# Vumetro.net
KiCad netlist of a schematic drawn in EAGLE
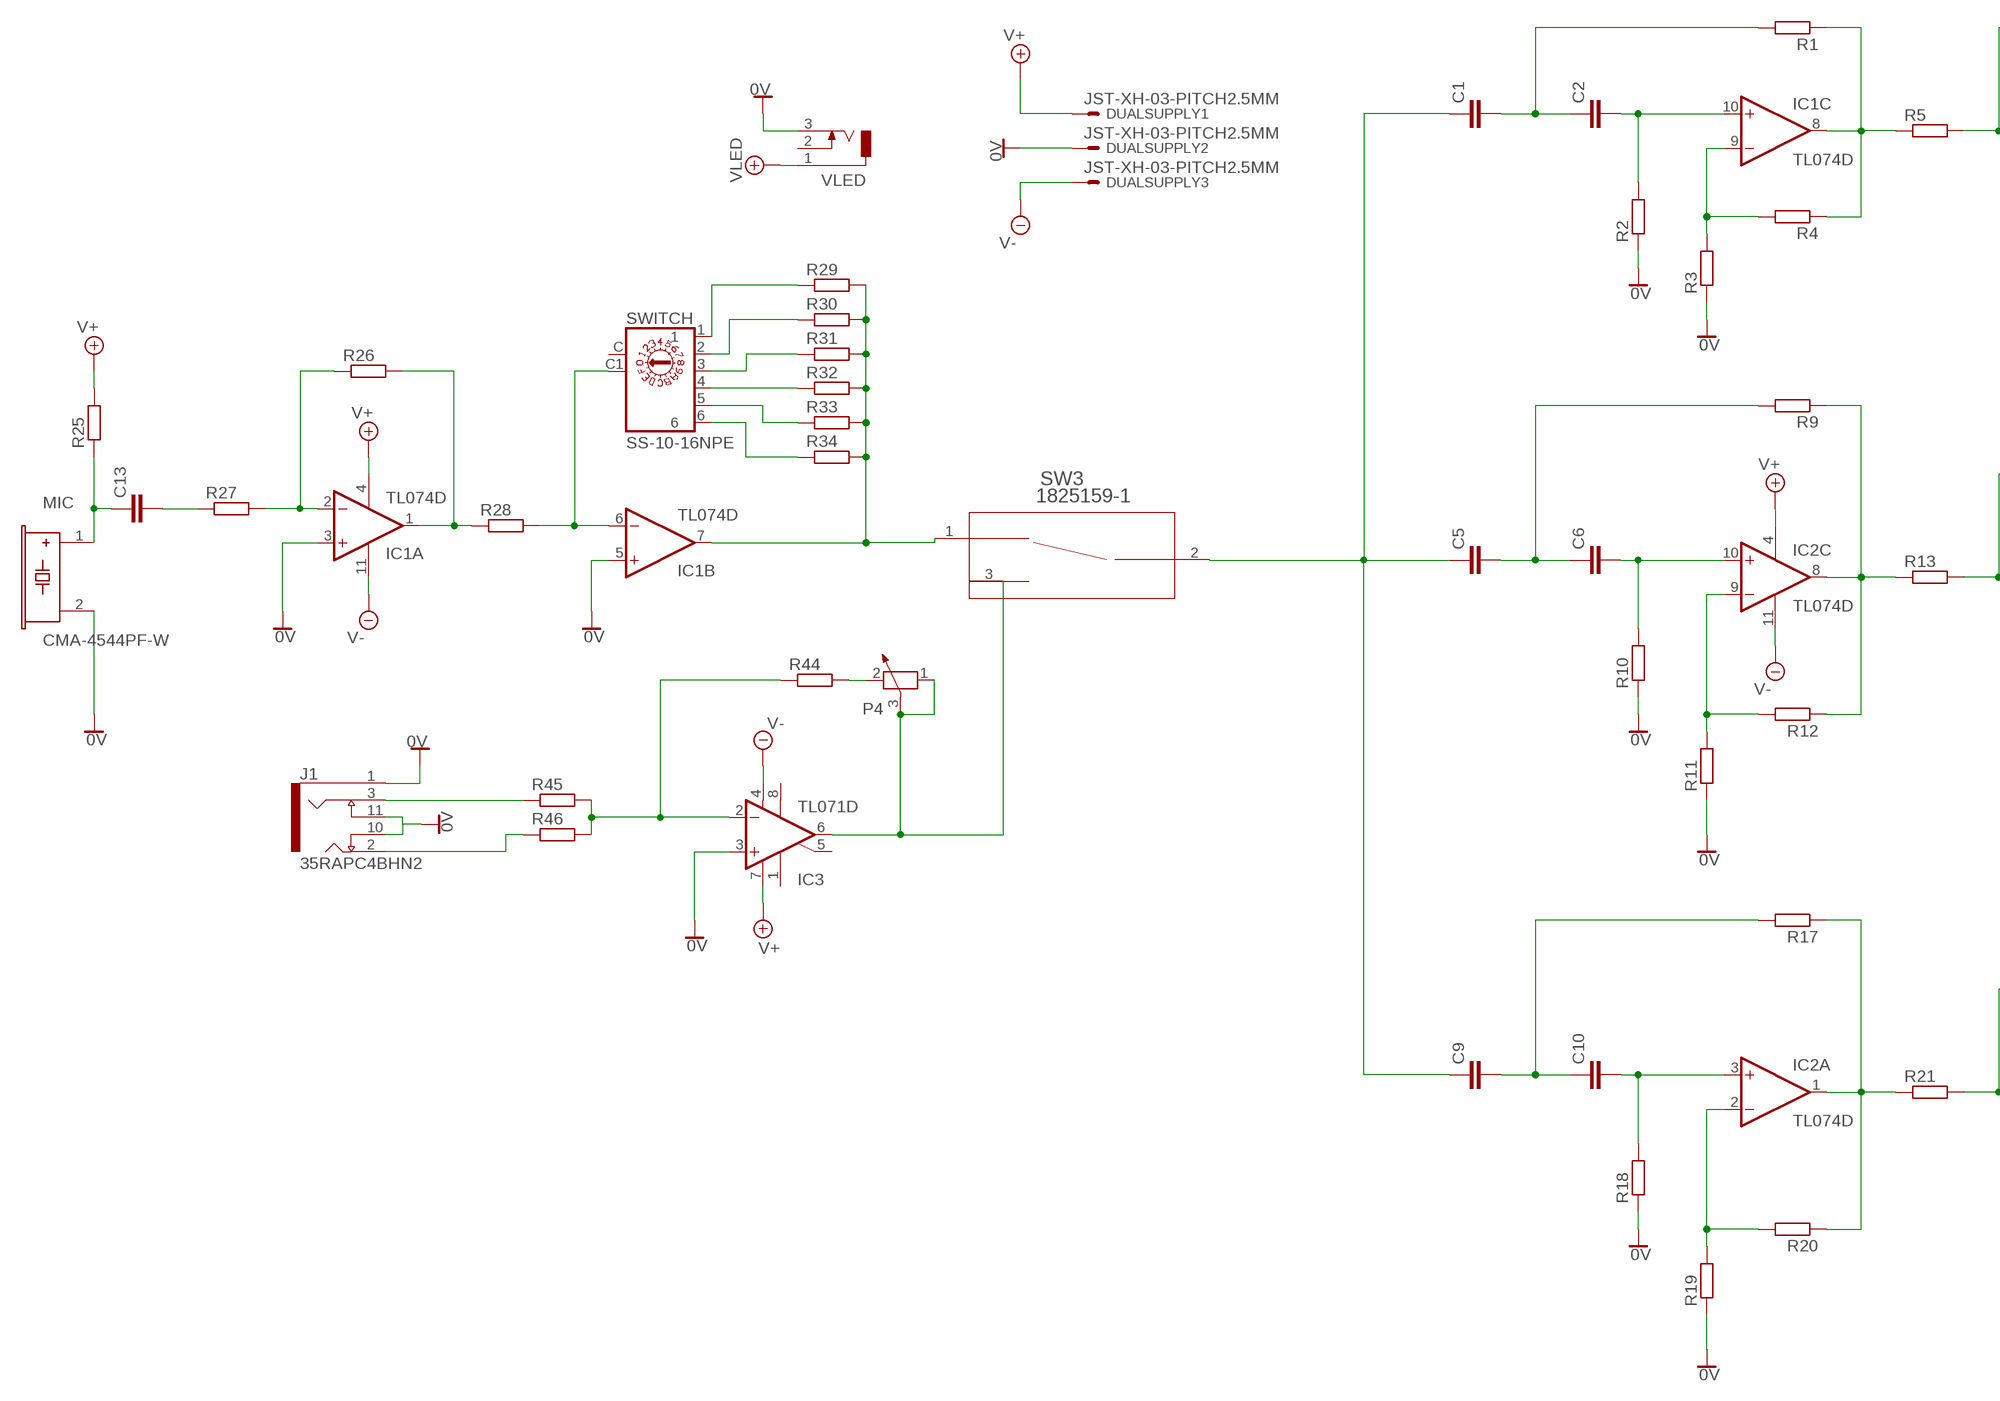
[diagram p0: schematic, sheet 1, part 1 of 2]
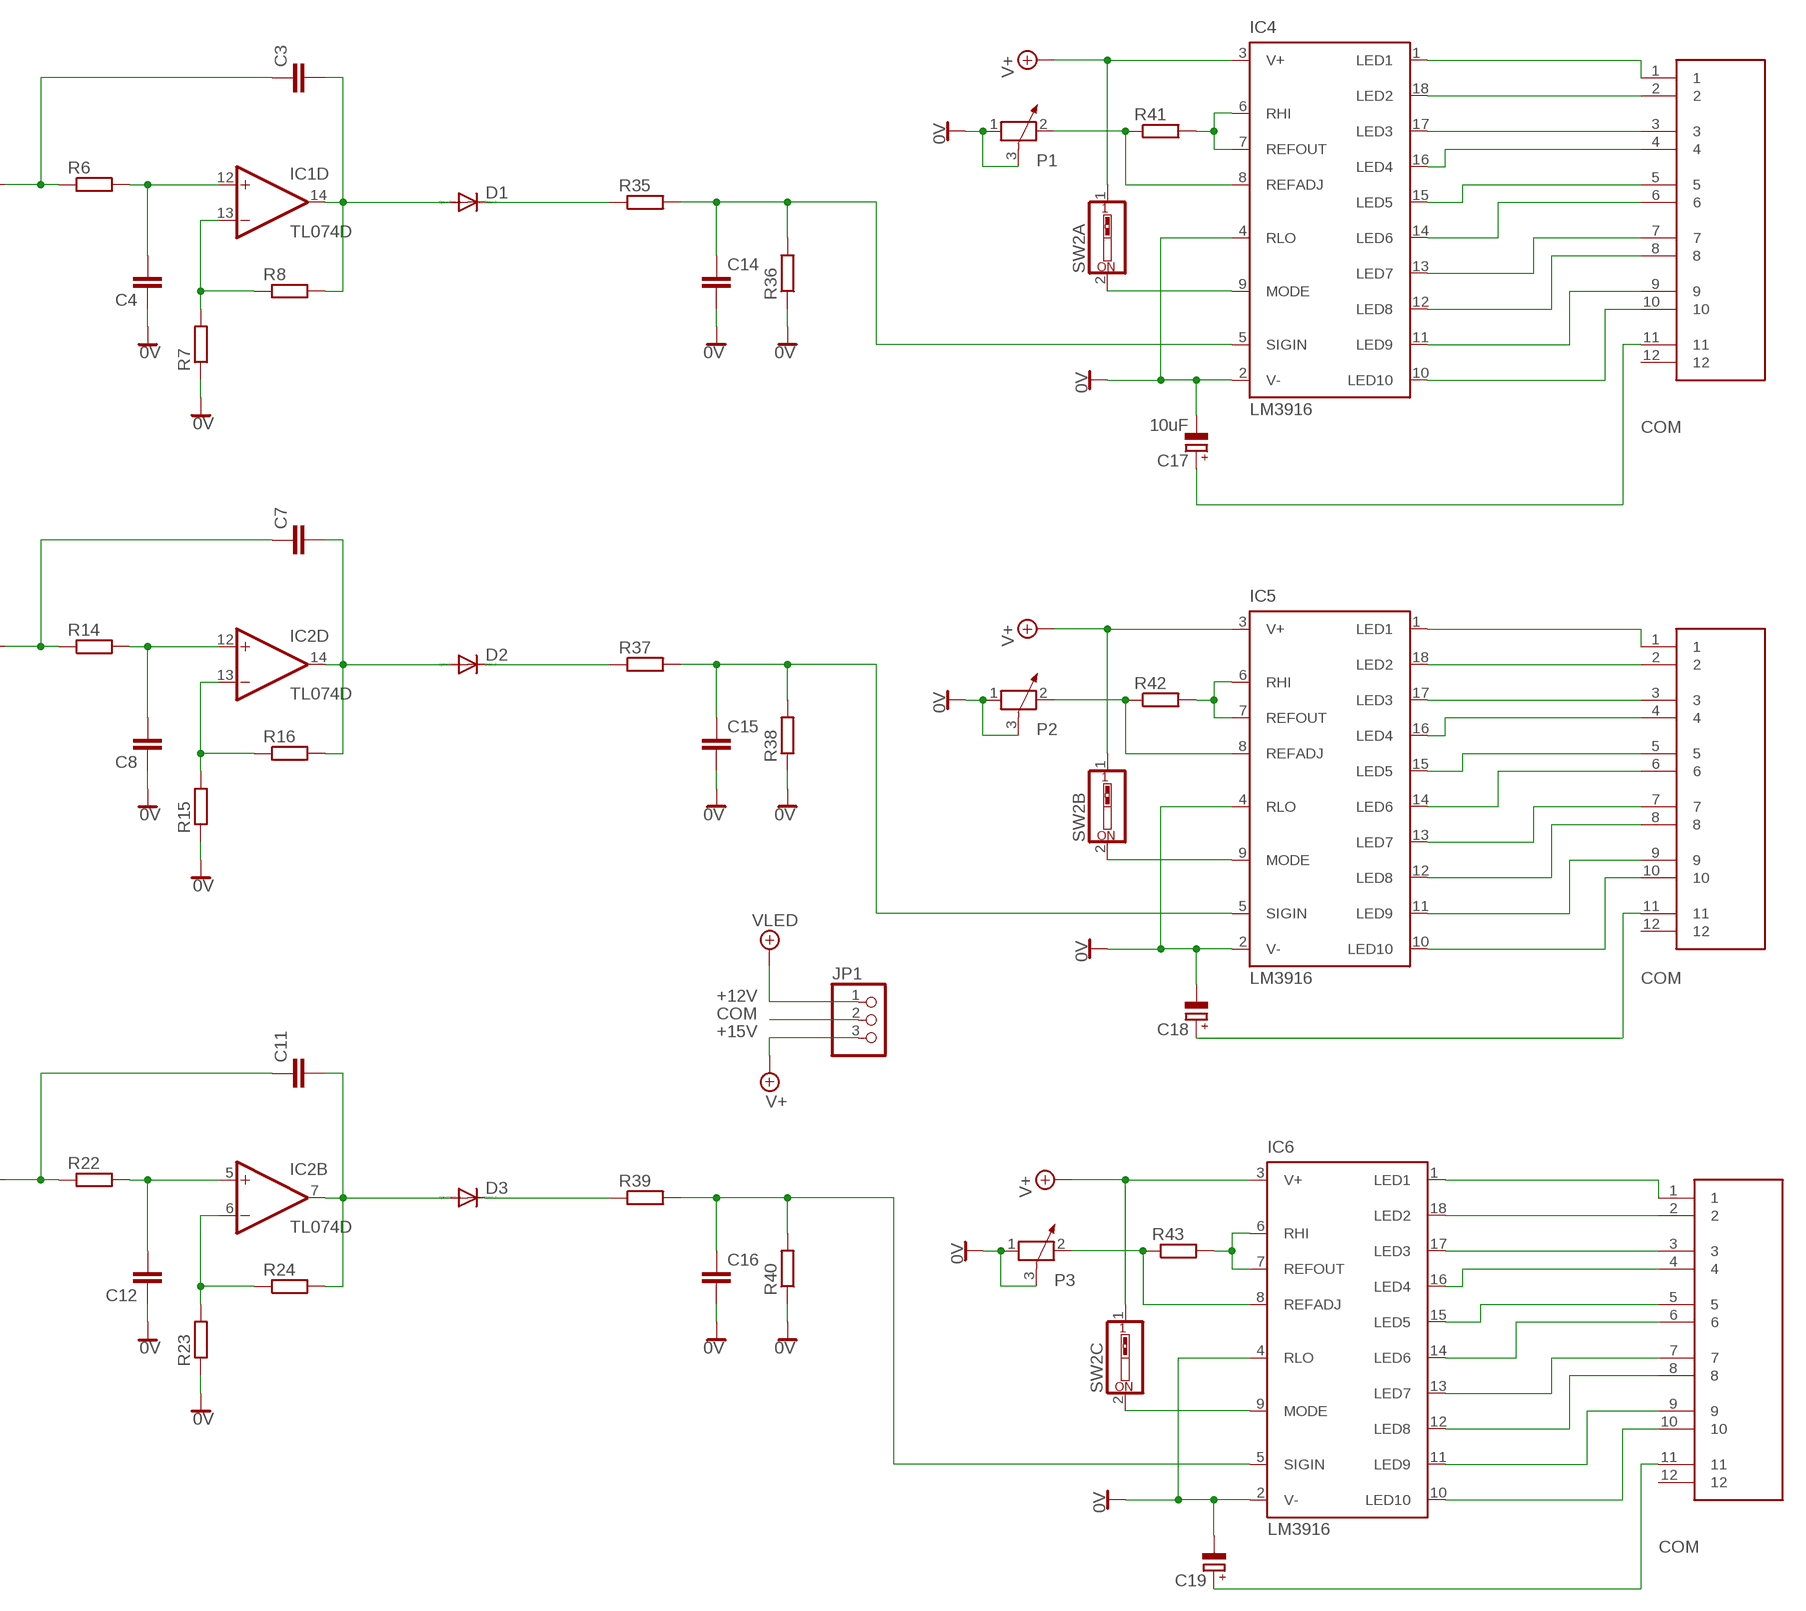
[diagram p1: schematic, sheet 1, part 2 of 2]

(export (version "E")
  (design (tool "Eeschema 10.0.6"))
  (components
    (comp (ref "C1")
      (value "C-EUC2012")
      (footprint "eagle-import:C2012")
      (libsource (lib "eagle-import") (part "C-EUC2012"))
    )
    (comp (ref "C2")
      (value "C-EUC2012")
      (footprint "eagle-import:C2012")
      (libsource (lib "eagle-import") (part "C-EUC2012"))
    )
    (comp (ref "C3")
      (value "C-EUC2012")
      (footprint "eagle-import:C2012")
      (libsource (lib "eagle-import") (part "C-EUC2012"))
    )
    (comp (ref "C4")
      (value "C-EUC2012")
      (footprint "eagle-import:C2012")
      (libsource (lib "eagle-import") (part "C-EUC2012"))
    )
    (comp (ref "C5")
      (value "C-EUC2012")
      (footprint "eagle-import:C2012")
      (libsource (lib "eagle-import") (part "C-EUC2012"))
    )
    (comp (ref "C6")
      (value "C-EUC2012")
      (footprint "eagle-import:C2012")
      (libsource (lib "eagle-import") (part "C-EUC2012"))
    )
    (comp (ref "C7")
      (value "C-EUC2012")
      (footprint "eagle-import:C2012")
      (libsource (lib "eagle-import") (part "C-EUC2012"))
    )
    (comp (ref "C8")
      (value "C-EUC2012")
      (footprint "eagle-import:C2012")
      (libsource (lib "eagle-import") (part "C-EUC2012"))
    )
    (comp (ref "C9")
      (value "C-EUC2012")
      (footprint "eagle-import:C2012")
      (libsource (lib "eagle-import") (part "C-EUC2012"))
    )
    (comp (ref "C10")
      (value "C-EUC2012")
      (footprint "eagle-import:C2012")
      (libsource (lib "eagle-import") (part "C-EUC2012"))
    )
    (comp (ref "C11")
      (value "C-EUC2012")
      (footprint "eagle-import:C2012")
      (libsource (lib "eagle-import") (part "C-EUC2012"))
    )
    (comp (ref "C12")
      (value "C-EUC2012")
      (footprint "eagle-import:C2012")
      (libsource (lib "eagle-import") (part "C-EUC2012"))
    )
    (comp (ref "C13")
      (value "C-EUC2012")
      (footprint "eagle-import:C2012")
      (libsource (lib "eagle-import") (part "C-EUC2012"))
    )
    (comp (ref "C14")
      (value "C-EUC2012")
      (footprint "eagle-import:C2012")
      (libsource (lib "eagle-import") (part "C-EUC2012"))
    )
    (comp (ref "C15")
      (value "C-EUC2012")
      (footprint "eagle-import:C2012")
      (libsource (lib "eagle-import") (part "C-EUC2012"))
    )
    (comp (ref "C16")
      (value "C-EUC2012")
      (footprint "eagle-import:C2012")
      (libsource (lib "eagle-import") (part "C-EUC2012"))
    )
    (comp (ref "C17")
      (value "10uF")
      (footprint "eagle-import:E2-4")
      (libsource (lib "eagle-import") (part "CPOL-EUE2-4"))
    )
    (comp (ref "C18")
      (value "CPOL-EUE2-4")
      (footprint "eagle-import:E2-4")
      (libsource (lib "eagle-import") (part "CPOL-EUE2-4"))
    )
    (comp (ref "C19")
      (value "CPOL-EUE2-4")
      (footprint "eagle-import:E2-4")
      (libsource (lib "eagle-import") (part "CPOL-EUE2-4"))
    )
    (comp (ref "CON1")
      (value "DF11-12DP-DIL")
      (footprint "eagle-import:CON_12_2X6_DIL_DF11")
      (libsource (lib "eagle-import") (part "DF11-12DP-DIL"))
    )
    (comp (ref "CON2")
      (value "DF11-12DP-DIL")
      (footprint "eagle-import:CON_12_2X6_DIL_DF11")
      (libsource (lib "eagle-import") (part "DF11-12DP-DIL"))
    )
    (comp (ref "CON3")
      (value "DF11-12DP-DIL")
      (footprint "eagle-import:CON_12_2X6_DIL_DF11")
      (libsource (lib "eagle-import") (part "DF11-12DP-DIL"))
    )
    (comp (ref "D1")
      (value "DIODE-SOD323-W")
      (footprint "eagle-import:SOD323-W")
      (libsource (lib "eagle-import") (part "DIODE-SOD323-W"))
    )
    (comp (ref "D2")
      (value "DIODE-SOD323-W")
      (footprint "eagle-import:SOD323-W")
      (libsource (lib "eagle-import") (part "DIODE-SOD323-W"))
    )
    (comp (ref "D3")
      (value "DIODE-SOD323-W")
      (footprint "eagle-import:SOD323-W")
      (libsource (lib "eagle-import") (part "DIODE-SOD323-W"))
    )
    (comp (ref "DUALSUPPLY")
      (value "JST-XH-03-PITCH2.5MM")
      (footprint "eagle-import:JST-XH-03-PITCH2.5MM")
      (libsource (lib "eagle-import") (part "JST-XH-03-PITCH2.5MM"))
    )
    (comp (ref "IC1")
      (value "TL074D")
      (footprint "eagle-import:SO14")
      (libsource (lib "eagle-import") (part "TL074D"))
    )
    (comp (ref "IC2")
      (value "TL074D")
      (footprint "eagle-import:SO14")
      (libsource (lib "eagle-import") (part "TL074D"))
    )
    (comp (ref "IC3")
      (value "TL071D")
      (footprint "eagle-import:SO08")
      (libsource (lib "eagle-import") (part "TL071D"))
    )
    (comp (ref "IC4")
      (value "LM3916")
      (footprint "eagle-import:DIL18")
      (libsource (lib "eagle-import") (part "LM3916"))
    )
    (comp (ref "IC5")
      (value "LM3916")
      (footprint "eagle-import:DIL18")
      (libsource (lib "eagle-import") (part "LM3916"))
    )
    (comp (ref "IC6")
      (value "LM3916")
      (footprint "eagle-import:DIL18")
      (libsource (lib "eagle-import") (part "LM3916"))
    )
    (comp (ref "J1")
      (value "35RAPC4BHN2")
      (footprint "eagle-import:SWITCHCRAFT_35RAPC4BHN2")
      (fields (field (name "DIGI-KEY_PART_NUMBER") "SC1459-ND") (field (name "MF") "Switchcraft"))
      (libsource (lib "eagle-import") (part "35RAPC4BHN2"))
    )
    (comp (ref "JP1")
      (value "PINHD-1X3")
      (footprint "eagle-import:1X03")
      (libsource (lib "eagle-import") (part "PINHD-1X3"))
    )
    (comp (ref "MIC")
      (value "CMA-4544PF-W")
      (footprint "eagle-import:CMA-4544PF-W")
      (fields (field (name "DIGI-KEY_PART_NUMBER") "102-1721-ND") (field (name "MF") "CUI"))
      (libsource (lib "eagle-import") (part "CMA-4544PF-W"))
    )
    (comp (ref "P1")
      (value "POTENTIOMETER_P090")
      (footprint "eagle-import:P090")
      (libsource (lib "eagle-import") (part "POTENTIOMETER_P090"))
    )
    (comp (ref "P2")
      (value "POTENTIOMETER_P090")
      (footprint "eagle-import:P090")
      (libsource (lib "eagle-import") (part "POTENTIOMETER_P090"))
    )
    (comp (ref "P3")
      (value "POTENTIOMETER_P090")
      (footprint "eagle-import:P090")
      (libsource (lib "eagle-import") (part "POTENTIOMETER_P090"))
    )
    (comp (ref "P4")
      (value "POTENTIOMETER_P090")
      (footprint "eagle-import:P090")
      (libsource (lib "eagle-import") (part "POTENTIOMETER_P090"))
    )
    (comp (ref "R1")
      (value "R-EU_R0805")
      (footprint "eagle-import:R0805")
      (libsource (lib "eagle-import") (part "R-EU_R0805"))
    )
    (comp (ref "R2")
      (value "R-EU_R0805")
      (footprint "eagle-import:R0805")
      (libsource (lib "eagle-import") (part "R-EU_R0805"))
    )
    (comp (ref "R3")
      (value "R-EU_R0805")
      (footprint "eagle-import:R0805")
      (libsource (lib "eagle-import") (part "R-EU_R0805"))
    )
    (comp (ref "R4")
      (value "R-EU_R0805")
      (footprint "eagle-import:R0805")
      (libsource (lib "eagle-import") (part "R-EU_R0805"))
    )
    (comp (ref "R5")
      (value "R-EU_R0805")
      (footprint "eagle-import:R0805")
      (libsource (lib "eagle-import") (part "R-EU_R0805"))
    )
    (comp (ref "R6")
      (value "R-EU_R0805")
      (footprint "eagle-import:R0805")
      (libsource (lib "eagle-import") (part "R-EU_R0805"))
    )
    (comp (ref "R7")
      (value "R-EU_R0805")
      (footprint "eagle-import:R0805")
      (libsource (lib "eagle-import") (part "R-EU_R0805"))
    )
    (comp (ref "R8")
      (value "R-EU_R0805")
      (footprint "eagle-import:R0805")
      (libsource (lib "eagle-import") (part "R-EU_R0805"))
    )
    (comp (ref "R9")
      (value "R-EU_R0805")
      (footprint "eagle-import:R0805")
      (libsource (lib "eagle-import") (part "R-EU_R0805"))
    )
    (comp (ref "R10")
      (value "R-EU_R0805")
      (footprint "eagle-import:R0805")
      (libsource (lib "eagle-import") (part "R-EU_R0805"))
    )
    (comp (ref "R11")
      (value "R-EU_R0805")
      (footprint "eagle-import:R0805")
      (libsource (lib "eagle-import") (part "R-EU_R0805"))
    )
    (comp (ref "R12")
      (value "R-EU_R0805")
      (footprint "eagle-import:R0805")
      (libsource (lib "eagle-import") (part "R-EU_R0805"))
    )
    (comp (ref "R13")
      (value "R-EU_R0805")
      (footprint "eagle-import:R0805")
      (libsource (lib "eagle-import") (part "R-EU_R0805"))
    )
    (comp (ref "R14")
      (value "R-EU_R0805")
      (footprint "eagle-import:R0805")
      (libsource (lib "eagle-import") (part "R-EU_R0805"))
    )
    (comp (ref "R15")
      (value "R-EU_R0805")
      (footprint "eagle-import:R0805")
      (libsource (lib "eagle-import") (part "R-EU_R0805"))
    )
    (comp (ref "R16")
      (value "R-EU_R0805")
      (footprint "eagle-import:R0805")
      (libsource (lib "eagle-import") (part "R-EU_R0805"))
    )
    (comp (ref "R17")
      (value "R-EU_M0805")
      (footprint "eagle-import:M0805")
      (libsource (lib "eagle-import") (part "R-EU_M0805"))
    )
    (comp (ref "R18")
      (value "R-EU_M0805")
      (footprint "eagle-import:M0805")
      (libsource (lib "eagle-import") (part "R-EU_M0805"))
    )
    (comp (ref "R19")
      (value "R-EU_M0805")
      (footprint "eagle-import:M0805")
      (libsource (lib "eagle-import") (part "R-EU_M0805"))
    )
    (comp (ref "R20")
      (value "R-EU_M0805")
      (footprint "eagle-import:M0805")
      (libsource (lib "eagle-import") (part "R-EU_M0805"))
    )
    (comp (ref "R21")
      (value "R-EU_M0805")
      (footprint "eagle-import:M0805")
      (libsource (lib "eagle-import") (part "R-EU_M0805"))
    )
    (comp (ref "R22")
      (value "R-EU_M0805")
      (footprint "eagle-import:M0805")
      (libsource (lib "eagle-import") (part "R-EU_M0805"))
    )
    (comp (ref "R23")
      (value "R-EU_M0805")
      (footprint "eagle-import:M0805")
      (libsource (lib "eagle-import") (part "R-EU_M0805"))
    )
    (comp (ref "R24")
      (value "R-EU_M0805")
      (footprint "eagle-import:M0805")
      (libsource (lib "eagle-import") (part "R-EU_M0805"))
    )
    (comp (ref "R25")
      (value "R-EU_R0805")
      (footprint "eagle-import:R0805")
      (libsource (lib "eagle-import") (part "R-EU_R0805"))
    )
    (comp (ref "R26")
      (value "R-EU_R0805")
      (footprint "eagle-import:R0805")
      (libsource (lib "eagle-import") (part "R-EU_R0805"))
    )
    (comp (ref "R27")
      (value "R-EU_R0805")
      (footprint "eagle-import:R0805")
      (libsource (lib "eagle-import") (part "R-EU_R0805"))
    )
    (comp (ref "R28")
      (value "R-EU_R0805")
      (footprint "eagle-import:R0805")
      (libsource (lib "eagle-import") (part "R-EU_R0805"))
    )
    (comp (ref "R29")
      (value "R-EU_R0805")
      (footprint "eagle-import:R0805")
      (libsource (lib "eagle-import") (part "R-EU_R0805"))
    )
    (comp (ref "R30")
      (value "R-EU_R0805")
      (footprint "eagle-import:R0805")
      (libsource (lib "eagle-import") (part "R-EU_R0805"))
    )
    (comp (ref "R31")
      (value "R-EU_R0805")
      (footprint "eagle-import:R0805")
      (libsource (lib "eagle-import") (part "R-EU_R0805"))
    )
    (comp (ref "R32")
      (value "R-EU_R0805")
      (footprint "eagle-import:R0805")
      (libsource (lib "eagle-import") (part "R-EU_R0805"))
    )
    (comp (ref "R33")
      (value "R-EU_R0805")
      (footprint "eagle-import:R0805")
      (libsource (lib "eagle-import") (part "R-EU_R0805"))
    )
    (comp (ref "R34")
      (value "R-EU_R0805")
      (footprint "eagle-import:R0805")
      (libsource (lib "eagle-import") (part "R-EU_R0805"))
    )
    (comp (ref "R35")
      (value "R-EU_R0805")
      (footprint "eagle-import:R0805")
      (libsource (lib "eagle-import") (part "R-EU_R0805"))
    )
    (comp (ref "R36")
      (value "R-EU_R0805")
      (footprint "eagle-import:R0805")
      (libsource (lib "eagle-import") (part "R-EU_R0805"))
    )
    (comp (ref "R37")
      (value "R-EU_R0805")
      (footprint "eagle-import:R0805")
      (libsource (lib "eagle-import") (part "R-EU_R0805"))
    )
    (comp (ref "R38")
      (value "R-EU_R0805")
      (footprint "eagle-import:R0805")
      (libsource (lib "eagle-import") (part "R-EU_R0805"))
    )
    (comp (ref "R39")
      (value "R-EU_R0805")
      (footprint "eagle-import:R0805")
      (libsource (lib "eagle-import") (part "R-EU_R0805"))
    )
    (comp (ref "R40")
      (value "R-EU_R0805")
      (footprint "eagle-import:R0805")
      (libsource (lib "eagle-import") (part "R-EU_R0805"))
    )
    (comp (ref "R41")
      (value "R-EU_M0805")
      (footprint "eagle-import:M0805")
      (libsource (lib "eagle-import") (part "R-EU_M0805"))
    )
    (comp (ref "R42")
      (value "R-EU_M0805")
      (footprint "eagle-import:M0805")
      (libsource (lib "eagle-import") (part "R-EU_M0805"))
    )
    (comp (ref "R43")
      (value "R-EU_M0805")
      (footprint "eagle-import:M0805")
      (libsource (lib "eagle-import") (part "R-EU_M0805"))
    )
    (comp (ref "R44")
      (value "R-EU_R0805")
      (footprint "eagle-import:R0805")
      (libsource (lib "eagle-import") (part "R-EU_R0805"))
    )
    (comp (ref "R45")
      (value "R-EU_R0805")
      (footprint "eagle-import:R0805")
      (libsource (lib "eagle-import") (part "R-EU_R0805"))
    )
    (comp (ref "R46")
      (value "R-EU_R0805")
      (footprint "eagle-import:R0805")
      (libsource (lib "eagle-import") (part "R-EU_R0805"))
    )
    (comp (ref "SW2A")
      (value "SW_DIP-1")
      (footprint "eagle-import:EDG-01")
      (libsource (lib "eagle-import") (part "SW_DIP-1"))
    )
    (comp (ref "SW2B")
      (value "SW_DIP-1")
      (footprint "eagle-import:EDG-01")
      (libsource (lib "eagle-import") (part "SW_DIP-1"))
    )
    (comp (ref "SW2C")
      (value "SW_DIP-1")
      (footprint "eagle-import:EDG-01")
      (libsource (lib "eagle-import") (part "SW_DIP-1"))
    )
    (comp (ref "SW3")
      (value "1825159-1")
      (footprint "eagle-import:SW3-SLIDE-2POL_P98")
      (fields (field (name "MANUFACTURER_PART_NUMBER") "18251591"))
      (libsource (lib "eagle-import") (part "1825159-1"))
    )
    (comp (ref "SWITCH")
      (value "SS-10-16NPE")
      (footprint "eagle-import:P106")
      (libsource (lib "eagle-import") (part "SS-10-16NPE"))
    )
    (comp (ref "VLED")
      (value "DCJ0303")
      (footprint "eagle-import:DCJ0303")
      (libsource (lib "eagle-import") (part "DCJ0303"))
    )
  )
  (nets
    (net (code "1") (name "/COM") (class "Default")
      (node (ref "C17") (pin "+") (pinfunction "+_+") (pintype "passive"))
      (node (ref "C18") (pin "+") (pinfunction "+_+") (pintype "passive"))
      (node (ref "C19") (pin "+") (pinfunction "+_+") (pintype "passive"))
      (node (ref "CON1") (pin "11") (pinfunction "11_11") (pintype "passive"))
      (node (ref "CON2") (pin "11") (pinfunction "11_11") (pintype "passive"))
      (node (ref "CON3") (pin "11") (pinfunction "11_11") (pintype "passive"))
      (node (ref "JP1") (pin "2") (pinfunction "2_2") (pintype "passive"))
    )
    (net (code "2") (name "0V") (class "Default")
      (node (ref "C12") (pin "1") (pinfunction "1_1") (pintype "passive"))
      (node (ref "C14") (pin "2") (pinfunction "2_2") (pintype "passive"))
      (node (ref "C15") (pin "2") (pinfunction "2_2") (pintype "passive"))
      (node (ref "C16") (pin "2") (pinfunction "2_2") (pintype "passive"))
      (node (ref "C17") (pin "-") (pinfunction "-_-") (pintype "passive"))
      (node (ref "C18") (pin "-") (pinfunction "-_-") (pintype "passive"))
      (node (ref "C19") (pin "-") (pinfunction "-_-") (pintype "passive"))
      (node (ref "C4") (pin "1") (pinfunction "1_1") (pintype "passive"))
      (node (ref "C8") (pin "1") (pinfunction "1_1") (pintype "passive"))
      (node (ref "DUALSUPPLY") (pin "2") (pinfunction "S_2") (pintype "passive"))
      (node (ref "IC1") (pin "3") (pinfunction "+IN_3") (pintype "input"))
      (node (ref "IC1") (pin "5") (pinfunction "+IN_5") (pintype "input"))
      (node (ref "IC3") (pin "3") (pinfunction "+IN_3") (pintype "input"))
      (node (ref "IC4") (pin "2") (pinfunction "V-_2") (pintype "power_in"))
      (node (ref "IC4") (pin "4") (pinfunction "RLO_4") (pintype "input"))
      (node (ref "IC5") (pin "2") (pinfunction "V-_2") (pintype "power_in"))
      (node (ref "IC5") (pin "4") (pinfunction "RLO_4") (pintype "input"))
      (node (ref "IC6") (pin "2") (pinfunction "V-_2") (pintype "power_in"))
      (node (ref "IC6") (pin "4") (pinfunction "RLO_4") (pintype "input"))
      (node (ref "J1") (pin "1") (pinfunction "SLEEVE_1") (pintype "passive"))
      (node (ref "J1") (pin "10") (pinfunction "TSH_10") (pintype "passive"))
      (node (ref "J1") (pin "11") (pinfunction "RSH_11") (pintype "passive"))
      (node (ref "MIC") (pin "2") (pinfunction "NEG_2") (pintype "bidirectional"))
      (node (ref "P1") (pin "1") (pinfunction "1_1") (pintype "passive"))
      (node (ref "P1") (pin "3") (pinfunction "3_3") (pintype "passive"))
      (node (ref "P2") (pin "1") (pinfunction "1_1") (pintype "passive"))
      (node (ref "P2") (pin "3") (pinfunction "3_3") (pintype "passive"))
      (node (ref "P3") (pin "1") (pinfunction "1_1") (pintype "passive"))
      (node (ref "P3") (pin "3") (pinfunction "3_3") (pintype "passive"))
      (node (ref "R10") (pin "1") (pinfunction "1_1") (pintype "passive"))
      (node (ref "R11") (pin "1") (pinfunction "1_1") (pintype "passive"))
      (node (ref "R15") (pin "1") (pinfunction "1_1") (pintype "passive"))
      (node (ref "R18") (pin "1") (pinfunction "1_1") (pintype "passive"))
      (node (ref "R19") (pin "1") (pinfunction "1_1") (pintype "passive"))
      (node (ref "R2") (pin "1") (pinfunction "1_1") (pintype "passive"))
      (node (ref "R23") (pin "1") (pinfunction "1_1") (pintype "passive"))
      (node (ref "R3") (pin "1") (pinfunction "1_1") (pintype "passive"))
      (node (ref "R36") (pin "1") (pinfunction "1_1") (pintype "passive"))
      (node (ref "R38") (pin "1") (pinfunction "1_1") (pintype "passive"))
      (node (ref "R40") (pin "1") (pinfunction "1_1") (pintype "passive"))
      (node (ref "R7") (pin "1") (pinfunction "1_1") (pintype "passive"))
      (node (ref "VLED") (pin "3") (pinfunction "3_3") (pintype "passive"))
    )
    (net (code "3") (name "Net-(C1-Pad2)") (class "Default")
      (node (ref "C1") (pin "2") (pinfunction "2_2") (pintype "passive"))
      (node (ref "C2") (pin "1") (pinfunction "1_1") (pintype "passive"))
      (node (ref "R1") (pin "2") (pinfunction "2_2") (pintype "passive"))
    )
    (net (code "4") (name "Net-(C3-Pad1)") (class "Default")
      (node (ref "C3") (pin "1") (pinfunction "1_1") (pintype "passive"))
      (node (ref "R5") (pin "2") (pinfunction "2_2") (pintype "passive"))
      (node (ref "R6") (pin "1") (pinfunction "1_1") (pintype "passive"))
    )
    (net (code "5") (name "Net-(C5-Pad2)") (class "Default")
      (node (ref "C5") (pin "2") (pinfunction "2_2") (pintype "passive"))
      (node (ref "C6") (pin "1") (pinfunction "1_1") (pintype "passive"))
      (node (ref "R9") (pin "2") (pinfunction "2_2") (pintype "passive"))
    )
    (net (code "6") (name "Net-(C7-Pad1)") (class "Default")
      (node (ref "C7") (pin "1") (pinfunction "1_1") (pintype "passive"))
      (node (ref "R13") (pin "2") (pinfunction "2_2") (pintype "passive"))
      (node (ref "R14") (pin "1") (pinfunction "1_1") (pintype "passive"))
    )
    (net (code "7") (name "Net-(C10-Pad1)") (class "Default")
      (node (ref "C10") (pin "1") (pinfunction "1_1") (pintype "passive"))
      (node (ref "C9") (pin "2") (pinfunction "2_2") (pintype "passive"))
      (node (ref "R17") (pin "2") (pinfunction "2_2") (pintype "passive"))
    )
    (net (code "8") (name "Net-(C11-Pad1)") (class "Default")
      (node (ref "C11") (pin "1") (pinfunction "1_1") (pintype "passive"))
      (node (ref "R21") (pin "2") (pinfunction "2_2") (pintype "passive"))
      (node (ref "R22") (pin "1") (pinfunction "1_1") (pintype "passive"))
    )
    (net (code "9") (name "Net-(C13-Pad2)") (class "Default")
      (node (ref "C13") (pin "2") (pinfunction "2_2") (pintype "passive"))
      (node (ref "R27") (pin "1") (pinfunction "1_1") (pintype "passive"))
    )
    (net (code "10") (name "Net-(D1-PadC)") (class "Default")
      (node (ref "D1") (pin "C") (pinfunction "C_C") (pintype "passive"))
      (node (ref "R35") (pin "1") (pinfunction "1_1") (pintype "passive"))
    )
    (net (code "11") (name "Net-(D2-PadC)") (class "Default")
      (node (ref "D2") (pin "C") (pinfunction "C_C") (pintype "passive"))
      (node (ref "R37") (pin "1") (pinfunction "1_1") (pintype "passive"))
    )
    (net (code "12") (name "Net-(D3-PadC)") (class "Default")
      (node (ref "D3") (pin "C") (pinfunction "C_C") (pintype "passive"))
      (node (ref "R39") (pin "1") (pinfunction "1_1") (pintype "passive"))
    )
    (net (code "13") (name "Net-(IC1A--IN)") (class "Default")
      (node (ref "IC1") (pin "2") (pinfunction "-IN_2") (pintype "input"))
      (node (ref "R26") (pin "1") (pinfunction "1_1") (pintype "passive"))
      (node (ref "R27") (pin "2") (pinfunction "2_2") (pintype "passive"))
    )
    (net (code "14") (name "Net-(IC1A-OUT)") (class "Default")
      (node (ref "IC1") (pin "1") (pinfunction "OUT_1") (pintype "output"))
      (node (ref "R26") (pin "2") (pinfunction "2_2") (pintype "passive"))
      (node (ref "R28") (pin "1") (pinfunction "1_1") (pintype "passive"))
    )
    (net (code "15") (name "Net-(IC1B--IN)") (class "Default")
      (node (ref "IC1") (pin "6") (pinfunction "-IN_6") (pintype "input"))
      (node (ref "R28") (pin "2") (pinfunction "2_2") (pintype "passive"))
      (node (ref "SWITCH") (pin "C1") (pinfunction "C1_C1") (pintype "passive"))
    )
    (net (code "16") (name "Net-(IC1B-OUT)") (class "Default")
      (node (ref "IC1") (pin "7") (pinfunction "OUT_7") (pintype "output"))
      (node (ref "R29") (pin "2") (pinfunction "2_2") (pintype "passive"))
      (node (ref "R30") (pin "2") (pinfunction "2_2") (pintype "passive"))
      (node (ref "R31") (pin "2") (pinfunction "2_2") (pintype "passive"))
      (node (ref "R32") (pin "2") (pinfunction "2_2") (pintype "passive"))
      (node (ref "R33") (pin "2") (pinfunction "2_2") (pintype "passive"))
      (node (ref "R34") (pin "2") (pinfunction "2_2") (pintype "passive"))
      (node (ref "SW3") (pin "1") (pinfunction "1_1") (pintype "passive"))
    )
    (net (code "17") (name "Net-(IC1C-+IN)") (class "Default")
      (node (ref "C2") (pin "2") (pinfunction "2_2") (pintype "passive"))
      (node (ref "IC1") (pin "10") (pinfunction "+IN_10") (pintype "input"))
      (node (ref "R2") (pin "2") (pinfunction "2_2") (pintype "passive"))
    )
    (net (code "18") (name "Net-(IC1C--IN)") (class "Default")
      (node (ref "IC1") (pin "9") (pinfunction "-IN_9") (pintype "input"))
      (node (ref "R3") (pin "2") (pinfunction "2_2") (pintype "passive"))
      (node (ref "R4") (pin "2") (pinfunction "2_2") (pintype "passive"))
    )
    (net (code "19") (name "Net-(IC1C-OUT)") (class "Default")
      (node (ref "IC1") (pin "8") (pinfunction "OUT_8") (pintype "output"))
      (node (ref "R1") (pin "1") (pinfunction "1_1") (pintype "passive"))
      (node (ref "R4") (pin "1") (pinfunction "1_1") (pintype "passive"))
      (node (ref "R5") (pin "1") (pinfunction "1_1") (pintype "passive"))
    )
    (net (code "20") (name "Net-(IC1D-+IN)") (class "Default")
      (node (ref "C4") (pin "2") (pinfunction "2_2") (pintype "passive"))
      (node (ref "IC1") (pin "12") (pinfunction "+IN_12") (pintype "input"))
      (node (ref "R6") (pin "2") (pinfunction "2_2") (pintype "passive"))
    )
    (net (code "21") (name "Net-(IC1D--IN)") (class "Default")
      (node (ref "IC1") (pin "13") (pinfunction "-IN_13") (pintype "input"))
      (node (ref "R7") (pin "2") (pinfunction "2_2") (pintype "passive"))
      (node (ref "R8") (pin "1") (pinfunction "1_1") (pintype "passive"))
    )
    (net (code "22") (name "Net-(IC1D-OUT)") (class "Default")
      (node (ref "C3") (pin "2") (pinfunction "2_2") (pintype "passive"))
      (node (ref "D1") (pin "A") (pinfunction "A_A") (pintype "passive"))
      (node (ref "IC1") (pin "14") (pinfunction "OUT_14") (pintype "output"))
      (node (ref "R8") (pin "2") (pinfunction "2_2") (pintype "passive"))
    )
    (net (code "23") (name "Net-(IC2A-+IN)") (class "Default")
      (node (ref "C10") (pin "2") (pinfunction "2_2") (pintype "passive"))
      (node (ref "IC2") (pin "3") (pinfunction "+IN_3") (pintype "input"))
      (node (ref "R18") (pin "2") (pinfunction "2_2") (pintype "passive"))
    )
    (net (code "24") (name "Net-(IC2A--IN)") (class "Default")
      (node (ref "IC2") (pin "2") (pinfunction "-IN_2") (pintype "input"))
      (node (ref "R19") (pin "2") (pinfunction "2_2") (pintype "passive"))
      (node (ref "R20") (pin "2") (pinfunction "2_2") (pintype "passive"))
    )
    (net (code "25") (name "Net-(IC2A-OUT)") (class "Default")
      (node (ref "IC2") (pin "1") (pinfunction "OUT_1") (pintype "output"))
      (node (ref "R17") (pin "1") (pinfunction "1_1") (pintype "passive"))
      (node (ref "R20") (pin "1") (pinfunction "1_1") (pintype "passive"))
      (node (ref "R21") (pin "1") (pinfunction "1_1") (pintype "passive"))
    )
    (net (code "26") (name "Net-(IC2B-+IN)") (class "Default")
      (node (ref "C12") (pin "2") (pinfunction "2_2") (pintype "passive"))
      (node (ref "IC2") (pin "5") (pinfunction "+IN_5") (pintype "input"))
      (node (ref "R22") (pin "2") (pinfunction "2_2") (pintype "passive"))
    )
    (net (code "27") (name "Net-(IC2B--IN)") (class "Default")
      (node (ref "IC2") (pin "6") (pinfunction "-IN_6") (pintype "input"))
      (node (ref "R23") (pin "2") (pinfunction "2_2") (pintype "passive"))
      (node (ref "R24") (pin "1") (pinfunction "1_1") (pintype "passive"))
    )
    (net (code "28") (name "Net-(IC2B-OUT)") (class "Default")
      (node (ref "C11") (pin "2") (pinfunction "2_2") (pintype "passive"))
      (node (ref "D3") (pin "A") (pinfunction "A_A") (pintype "passive"))
      (node (ref "IC2") (pin "7") (pinfunction "OUT_7") (pintype "output"))
      (node (ref "R24") (pin "2") (pinfunction "2_2") (pintype "passive"))
    )
    (net (code "29") (name "Net-(IC2C-+IN)") (class "Default")
      (node (ref "C6") (pin "2") (pinfunction "2_2") (pintype "passive"))
      (node (ref "IC2") (pin "10") (pinfunction "+IN_10") (pintype "input"))
      (node (ref "R10") (pin "2") (pinfunction "2_2") (pintype "passive"))
    )
    (net (code "30") (name "Net-(IC2C--IN)") (class "Default")
      (node (ref "IC2") (pin "9") (pinfunction "-IN_9") (pintype "input"))
      (node (ref "R11") (pin "2") (pinfunction "2_2") (pintype "passive"))
      (node (ref "R12") (pin "2") (pinfunction "2_2") (pintype "passive"))
    )
    (net (code "31") (name "Net-(IC2C-OUT)") (class "Default")
      (node (ref "IC2") (pin "8") (pinfunction "OUT_8") (pintype "output"))
      (node (ref "R12") (pin "1") (pinfunction "1_1") (pintype "passive"))
      (node (ref "R13") (pin "1") (pinfunction "1_1") (pintype "passive"))
      (node (ref "R9") (pin "1") (pinfunction "1_1") (pintype "passive"))
    )
    (net (code "32") (name "Net-(IC2D-+IN)") (class "Default")
      (node (ref "C8") (pin "2") (pinfunction "2_2") (pintype "passive"))
      (node (ref "IC2") (pin "12") (pinfunction "+IN_12") (pintype "input"))
      (node (ref "R14") (pin "2") (pinfunction "2_2") (pintype "passive"))
    )
    (net (code "33") (name "Net-(IC2D--IN)") (class "Default")
      (node (ref "IC2") (pin "13") (pinfunction "-IN_13") (pintype "input"))
      (node (ref "R15") (pin "2") (pinfunction "2_2") (pintype "passive"))
      (node (ref "R16") (pin "1") (pinfunction "1_1") (pintype "passive"))
    )
    (net (code "34") (name "Net-(IC2D-OUT)") (class "Default")
      (node (ref "C7") (pin "2") (pinfunction "2_2") (pintype "passive"))
      (node (ref "D2") (pin "A") (pinfunction "A_A") (pintype "passive"))
      (node (ref "IC2") (pin "14") (pinfunction "OUT_14") (pintype "output"))
      (node (ref "R16") (pin "2") (pinfunction "2_2") (pintype "passive"))
    )
    (net (code "35") (name "Net-(IC3--IN)") (class "Default")
      (node (ref "IC3") (pin "2") (pinfunction "-IN_2") (pintype "input"))
      (node (ref "R44") (pin "1") (pinfunction "1_1") (pintype "passive"))
      (node (ref "R45") (pin "2") (pinfunction "2_2") (pintype "passive"))
      (node (ref "R46") (pin "2") (pinfunction "2_2") (pintype "passive"))
    )
    (net (code "36") (name "Net-(IC3-OUT)") (class "Default")
      (node (ref "IC3") (pin "6") (pinfunction "OUT_6") (pintype "output"))
      (node (ref "P4") (pin "1") (pinfunction "1_1") (pintype "passive"))
      (node (ref "P4") (pin "3") (pinfunction "3_3") (pintype "passive"))
      (node (ref "SW3") (pin "3") (pinfunction "2_3") (pintype "passive"))
    )
    (net (code "37") (name "Net-(IC4-LED1)") (class "Default")
      (node (ref "CON1") (pin "1") (pinfunction "1_1") (pintype "passive"))
      (node (ref "IC4") (pin "1") (pinfunction "LED1_1") (pintype "output"))
    )
    (net (code "38") (name "Net-(IC4-LED2)") (class "Default")
      (node (ref "CON1") (pin "2") (pinfunction "2_2") (pintype "passive"))
      (node (ref "IC4") (pin "18") (pinfunction "LED2_18") (pintype "output"))
    )
    (net (code "39") (name "Net-(IC4-LED3)") (class "Default")
      (node (ref "CON1") (pin "3") (pinfunction "3_3") (pintype "passive"))
      (node (ref "IC4") (pin "17") (pinfunction "LED3_17") (pintype "output"))
    )
    (net (code "40") (name "Net-(IC4-LED4)") (class "Default")
      (node (ref "CON1") (pin "4") (pinfunction "4_4") (pintype "passive"))
      (node (ref "IC4") (pin "16") (pinfunction "LED4_16") (pintype "output"))
    )
    (net (code "41") (name "Net-(IC4-LED5)") (class "Default")
      (node (ref "CON1") (pin "5") (pinfunction "5_5") (pintype "passive"))
      (node (ref "IC4") (pin "15") (pinfunction "LED5_15") (pintype "output"))
    )
    (net (code "42") (name "Net-(IC4-LED6)") (class "Default")
      (node (ref "CON1") (pin "6") (pinfunction "6_6") (pintype "passive"))
      (node (ref "IC4") (pin "14") (pinfunction "LED6_14") (pintype "output"))
    )
    (net (code "43") (name "Net-(IC4-LED7)") (class "Default")
      (node (ref "CON1") (pin "7") (pinfunction "7_7") (pintype "passive"))
      (node (ref "IC4") (pin "13") (pinfunction "LED7_13") (pintype "output"))
    )
    (net (code "44") (name "Net-(IC4-LED8)") (class "Default")
      (node (ref "CON1") (pin "8") (pinfunction "8_8") (pintype "passive"))
      (node (ref "IC4") (pin "12") (pinfunction "LED8_12") (pintype "output"))
    )
    (net (code "45") (name "Net-(IC4-LED9)") (class "Default")
      (node (ref "CON1") (pin "9") (pinfunction "9_9") (pintype "passive"))
      (node (ref "IC4") (pin "11") (pinfunction "LED9_11") (pintype "output"))
    )
    (net (code "46") (name "Net-(IC4-LED10)") (class "Default")
      (node (ref "CON1") (pin "10") (pinfunction "10_10") (pintype "passive"))
      (node (ref "IC4") (pin "10") (pinfunction "LED10_10") (pintype "output"))
    )
    (net (code "47") (name "Net-(IC4-MODE)") (class "Default")
      (node (ref "IC4") (pin "9") (pinfunction "MODE_9") (pintype "input"))
      (node (ref "SW2A") (pin "2") (pinfunction "2_2") (pintype "passive"))
    )
    (net (code "48") (name "Net-(IC4-REFADJ)") (class "Default")
      (node (ref "IC4") (pin "8") (pinfunction "REFADJ_8") (pintype "passive"))
      (node (ref "P1") (pin "2") (pinfunction "2_2") (pintype "passive"))
      (node (ref "R41") (pin "1") (pinfunction "1_1") (pintype "passive"))
    )
    (net (code "49") (name "Net-(IC4-REFOUT)") (class "Default")
      (node (ref "IC4") (pin "6") (pinfunction "RHI_6") (pintype "input"))
      (node (ref "IC4") (pin "7") (pinfunction "REFOUT_7") (pintype "output"))
      (node (ref "R41") (pin "2") (pinfunction "2_2") (pintype "passive"))
    )
    (net (code "50") (name "Net-(IC4-SIGIN)") (class "Default")
      (node (ref "C14") (pin "1") (pinfunction "1_1") (pintype "passive"))
      (node (ref "IC4") (pin "5") (pinfunction "SIGIN_5") (pintype "input"))
      (node (ref "R35") (pin "2") (pinfunction "2_2") (pintype "passive"))
      (node (ref "R36") (pin "2") (pinfunction "2_2") (pintype "passive"))
    )
    (net (code "51") (name "Net-(IC5-LED1)") (class "Default")
      (node (ref "CON2") (pin "1") (pinfunction "1_1") (pintype "passive"))
      (node (ref "IC5") (pin "1") (pinfunction "LED1_1") (pintype "output"))
    )
    (net (code "52") (name "Net-(IC5-LED2)") (class "Default")
      (node (ref "CON2") (pin "2") (pinfunction "2_2") (pintype "passive"))
      (node (ref "IC5") (pin "18") (pinfunction "LED2_18") (pintype "output"))
    )
    (net (code "53") (name "Net-(IC5-LED3)") (class "Default")
      (node (ref "CON2") (pin "3") (pinfunction "3_3") (pintype "passive"))
      (node (ref "IC5") (pin "17") (pinfunction "LED3_17") (pintype "output"))
    )
    (net (code "54") (name "Net-(IC5-LED4)") (class "Default")
      (node (ref "CON2") (pin "4") (pinfunction "4_4") (pintype "passive"))
      (node (ref "IC5") (pin "16") (pinfunction "LED4_16") (pintype "output"))
    )
    (net (code "55") (name "Net-(IC5-LED5)") (class "Default")
      (node (ref "CON2") (pin "5") (pinfunction "5_5") (pintype "passive"))
      (node (ref "IC5") (pin "15") (pinfunction "LED5_15") (pintype "output"))
    )
    (net (code "56") (name "Net-(IC5-LED6)") (class "Default")
      (node (ref "CON2") (pin "6") (pinfunction "6_6") (pintype "passive"))
      (node (ref "IC5") (pin "14") (pinfunction "LED6_14") (pintype "output"))
    )
    (net (code "57") (name "Net-(IC5-LED7)") (class "Default")
      (node (ref "CON2") (pin "7") (pinfunction "7_7") (pintype "passive"))
      (node (ref "IC5") (pin "13") (pinfunction "LED7_13") (pintype "output"))
    )
    (net (code "58") (name "Net-(IC5-LED8)") (class "Default")
      (node (ref "CON2") (pin "8") (pinfunction "8_8") (pintype "passive"))
      (node (ref "IC5") (pin "12") (pinfunction "LED8_12") (pintype "output"))
    )
    (net (code "59") (name "Net-(IC5-LED9)") (class "Default")
      (node (ref "CON2") (pin "9") (pinfunction "9_9") (pintype "passive"))
      (node (ref "IC5") (pin "11") (pinfunction "LED9_11") (pintype "output"))
    )
    (net (code "60") (name "Net-(IC5-LED10)") (class "Default")
      (node (ref "CON2") (pin "10") (pinfunction "10_10") (pintype "passive"))
      (node (ref "IC5") (pin "10") (pinfunction "LED10_10") (pintype "output"))
    )
    (net (code "61") (name "Net-(IC5-MODE)") (class "Default")
      (node (ref "IC5") (pin "9") (pinfunction "MODE_9") (pintype "input"))
      (node (ref "SW2B") (pin "2") (pinfunction "2_2") (pintype "passive"))
    )
    (net (code "62") (name "Net-(IC5-REFADJ)") (class "Default")
      (node (ref "IC5") (pin "8") (pinfunction "REFADJ_8") (pintype "passive"))
      (node (ref "P2") (pin "2") (pinfunction "2_2") (pintype "passive"))
      (node (ref "R42") (pin "1") (pinfunction "1_1") (pintype "passive"))
    )
    (net (code "63") (name "Net-(IC5-REFOUT)") (class "Default")
      (node (ref "IC5") (pin "6") (pinfunction "RHI_6") (pintype "input"))
      (node (ref "IC5") (pin "7") (pinfunction "REFOUT_7") (pintype "output"))
      (node (ref "R42") (pin "2") (pinfunction "2_2") (pintype "passive"))
    )
    (net (code "64") (name "Net-(IC5-SIGIN)") (class "Default")
      (node (ref "C15") (pin "1") (pinfunction "1_1") (pintype "passive"))
      (node (ref "IC5") (pin "5") (pinfunction "SIGIN_5") (pintype "input"))
      (node (ref "R37") (pin "2") (pinfunction "2_2") (pintype "passive"))
      (node (ref "R38") (pin "2") (pinfunction "2_2") (pintype "passive"))
    )
    (net (code "65") (name "Net-(IC6-LED1)") (class "Default")
      (node (ref "CON3") (pin "1") (pinfunction "1_1") (pintype "passive"))
      (node (ref "IC6") (pin "1") (pinfunction "LED1_1") (pintype "output"))
    )
    (net (code "66") (name "Net-(IC6-LED2)") (class "Default")
      (node (ref "CON3") (pin "2") (pinfunction "2_2") (pintype "passive"))
      (node (ref "IC6") (pin "18") (pinfunction "LED2_18") (pintype "output"))
    )
    (net (code "67") (name "Net-(IC6-LED3)") (class "Default")
      (node (ref "CON3") (pin "3") (pinfunction "3_3") (pintype "passive"))
      (node (ref "IC6") (pin "17") (pinfunction "LED3_17") (pintype "output"))
    )
    (net (code "68") (name "Net-(IC6-LED4)") (class "Default")
      (node (ref "CON3") (pin "4") (pinfunction "4_4") (pintype "passive"))
      (node (ref "IC6") (pin "16") (pinfunction "LED4_16") (pintype "output"))
    )
    (net (code "69") (name "Net-(IC6-LED5)") (class "Default")
      (node (ref "CON3") (pin "5") (pinfunction "5_5") (pintype "passive"))
      (node (ref "IC6") (pin "15") (pinfunction "LED5_15") (pintype "output"))
    )
    (net (code "70") (name "Net-(IC6-LED6)") (class "Default")
      (node (ref "CON3") (pin "6") (pinfunction "6_6") (pintype "passive"))
      (node (ref "IC6") (pin "14") (pinfunction "LED6_14") (pintype "output"))
    )
    (net (code "71") (name "Net-(IC6-LED7)") (class "Default")
      (node (ref "CON3") (pin "7") (pinfunction "7_7") (pintype "passive"))
      (node (ref "IC6") (pin "13") (pinfunction "LED7_13") (pintype "output"))
    )
    (net (code "72") (name "Net-(IC6-LED8)") (class "Default")
      (node (ref "CON3") (pin "8") (pinfunction "8_8") (pintype "passive"))
      (node (ref "IC6") (pin "12") (pinfunction "LED8_12") (pintype "output"))
    )
    (net (code "73") (name "Net-(IC6-LED9)") (class "Default")
      (node (ref "CON3") (pin "9") (pinfunction "9_9") (pintype "passive"))
      (node (ref "IC6") (pin "11") (pinfunction "LED9_11") (pintype "output"))
    )
    (net (code "74") (name "Net-(IC6-LED10)") (class "Default")
      (node (ref "CON3") (pin "10") (pinfunction "10_10") (pintype "passive"))
      (node (ref "IC6") (pin "10") (pinfunction "LED10_10") (pintype "output"))
    )
    (net (code "75") (name "Net-(IC6-MODE)") (class "Default")
      (node (ref "IC6") (pin "9") (pinfunction "MODE_9") (pintype "input"))
      (node (ref "SW2C") (pin "2") (pinfunction "2_2") (pintype "passive"))
    )
    (net (code "76") (name "Net-(IC6-REFADJ)") (class "Default")
      (node (ref "IC6") (pin "8") (pinfunction "REFADJ_8") (pintype "passive"))
      (node (ref "P3") (pin "2") (pinfunction "2_2") (pintype "passive"))
      (node (ref "R43") (pin "1") (pinfunction "1_1") (pintype "passive"))
    )
    (net (code "77") (name "Net-(IC6-REFOUT)") (class "Default")
      (node (ref "IC6") (pin "6") (pinfunction "RHI_6") (pintype "input"))
      (node (ref "IC6") (pin "7") (pinfunction "REFOUT_7") (pintype "output"))
      (node (ref "R43") (pin "2") (pinfunction "2_2") (pintype "passive"))
    )
    (net (code "78") (name "Net-(IC6-SIGIN)") (class "Default")
      (node (ref "C16") (pin "1") (pinfunction "1_1") (pintype "passive"))
      (node (ref "IC6") (pin "5") (pinfunction "SIGIN_5") (pintype "input"))
      (node (ref "R39") (pin "2") (pinfunction "2_2") (pintype "passive"))
      (node (ref "R40") (pin "2") (pinfunction "2_2") (pintype "passive"))
    )
    (net (code "79") (name "Net-(J1-RING)") (class "Default")
      (node (ref "J1") (pin "3") (pinfunction "RING_3") (pintype "passive"))
      (node (ref "R45") (pin "1") (pinfunction "1_1") (pintype "passive"))
    )
    (net (code "80") (name "Net-(J1-TIP)") (class "Default")
      (node (ref "J1") (pin "2") (pinfunction "TIP_2") (pintype "passive"))
      (node (ref "R46") (pin "1") (pinfunction "1_1") (pintype "passive"))
    )
    (net (code "81") (name "Net-(MIC-POS)") (class "Default")
      (node (ref "C13") (pin "1") (pinfunction "1_1") (pintype "passive"))
      (node (ref "MIC") (pin "1") (pinfunction "POS_1") (pintype "bidirectional"))
      (node (ref "R25") (pin "1") (pinfunction "1_1") (pintype "passive"))
    )
    (net (code "82") (name "Net-(P4-Pad2)") (class "Default")
      (node (ref "P4") (pin "2") (pinfunction "2_2") (pintype "passive"))
      (node (ref "R44") (pin "2") (pinfunction "2_2") (pintype "passive"))
    )
    (net (code "83") (name "Net-(R29-Pad1)") (class "Default")
      (node (ref "R29") (pin "1") (pinfunction "1_1") (pintype "passive"))
      (node (ref "SWITCH") (pin "1") (pinfunction "1_1") (pintype "passive"))
    )
    (net (code "84") (name "Net-(R30-Pad1)") (class "Default")
      (node (ref "R30") (pin "1") (pinfunction "1_1") (pintype "passive"))
      (node (ref "SWITCH") (pin "2") (pinfunction "2_2") (pintype "passive"))
    )
    (net (code "85") (name "Net-(R31-Pad1)") (class "Default")
      (node (ref "R31") (pin "1") (pinfunction "1_1") (pintype "passive"))
      (node (ref "SWITCH") (pin "3") (pinfunction "3_3") (pintype "passive"))
    )
    (net (code "86") (name "Net-(R32-Pad1)") (class "Default")
      (node (ref "R32") (pin "1") (pinfunction "1_1") (pintype "passive"))
      (node (ref "SWITCH") (pin "4") (pinfunction "4_4") (pintype "passive"))
    )
    (net (code "87") (name "Net-(R33-Pad1)") (class "Default")
      (node (ref "R33") (pin "1") (pinfunction "1_1") (pintype "passive"))
      (node (ref "SWITCH") (pin "5") (pinfunction "5_5") (pintype "passive"))
    )
    (net (code "88") (name "Net-(R34-Pad1)") (class "Default")
      (node (ref "R34") (pin "1") (pinfunction "1_1") (pintype "passive"))
      (node (ref "SWITCH") (pin "6") (pinfunction "6_6") (pintype "passive"))
    )
    (net (code "89") (name "Net-(SW3-3)") (class "Default")
      (node (ref "C1") (pin "1") (pinfunction "1_1") (pintype "passive"))
      (node (ref "C5") (pin "1") (pinfunction "1_1") (pintype "passive"))
      (node (ref "C9") (pin "1") (pinfunction "1_1") (pintype "passive"))
      (node (ref "SW3") (pin "2") (pinfunction "3_2") (pintype "passive"))
    )
    (net (code "90") (name "V+") (class "Default")
      (node (ref "DUALSUPPLY") (pin "1") (pinfunction "S_1") (pintype "passive"))
      (node (ref "IC1") (pin "4") (pinfunction "V+_4") (pintype "power_in"))
      (node (ref "IC2") (pin "4") (pinfunction "V+_4") (pintype "power_in"))
      (node (ref "IC3") (pin "7") (pinfunction "V+_7") (pintype "power_in"))
      (node (ref "IC4") (pin "3") (pinfunction "V+_3") (pintype "power_in"))
      (node (ref "IC5") (pin "3") (pinfunction "V+_3") (pintype "power_in"))
      (node (ref "IC6") (pin "3") (pinfunction "V+_3") (pintype "power_in"))
      (node (ref "JP1") (pin "3") (pinfunction "3_3") (pintype "passive"))
      (node (ref "R25") (pin "2") (pinfunction "2_2") (pintype "passive"))
      (node (ref "SW2A") (pin "1") (pinfunction "1_1") (pintype "passive"))
      (node (ref "SW2B") (pin "1") (pinfunction "1_1") (pintype "passive"))
      (node (ref "SW2C") (pin "1") (pinfunction "1_1") (pintype "passive"))
    )
    (net (code "91") (name "V-") (class "Default")
      (node (ref "DUALSUPPLY") (pin "3") (pinfunction "S_3") (pintype "passive"))
      (node (ref "IC1") (pin "11") (pinfunction "V-_11") (pintype "power_in"))
      (node (ref "IC2") (pin "11") (pinfunction "V-_11") (pintype "power_in"))
      (node (ref "IC3") (pin "4") (pinfunction "V-_4") (pintype "power_in"))
    )
    (net (code "92") (name "VLED") (class "Default")
      (node (ref "JP1") (pin "1") (pinfunction "1_1") (pintype "passive"))
      (node (ref "VLED") (pin "1") (pinfunction "1_1") (pintype "passive"))
    )
    (net (code "93") (name "unconnected-(CON1-Pad12)") (class "Default")
      (node (ref "CON1") (pin "12") (pinfunction "12_12") (pintype "passive"))
    )
    (net (code "94") (name "unconnected-(CON2-Pad12)") (class "Default")
      (node (ref "CON2") (pin "12") (pinfunction "12_12") (pintype "passive"))
    )
    (net (code "95") (name "unconnected-(CON3-Pad12)") (class "Default")
      (node (ref "CON3") (pin "12") (pinfunction "12_12") (pintype "passive"))
    )
    (net (code "96") (name "unconnected-(IC3-ON1-Pad1)") (class "Default")
      (node (ref "IC3") (pin "1") (pinfunction "ON1_1") (pintype "passive"))
    )
    (net (code "97") (name "unconnected-(IC3-ON2-Pad5)") (class "Default")
      (node (ref "IC3") (pin "5") (pinfunction "ON2_5") (pintype "passive"))
    )
    (net (code "98") (name "unconnected-(IC3-OPT-Pad8)") (class "Default")
      (node (ref "IC3") (pin "8") (pinfunction "OPT_8") (pintype "passive"))
    )
    (net (code "99") (name "unconnected-(SWITCH-PadC)") (class "Default")
      (node (ref "SWITCH") (pin "C") (pinfunction "C_C") (pintype "passive"))
    )
    (net (code "100") (name "unconnected-(VLED-Pad2)") (class "Default")
      (node (ref "VLED") (pin "2") (pinfunction "2_2") (pintype "passive"))
    )
  )
)
